# OLED.net
KiCad netlist of a schematic drawn in Altium Designer
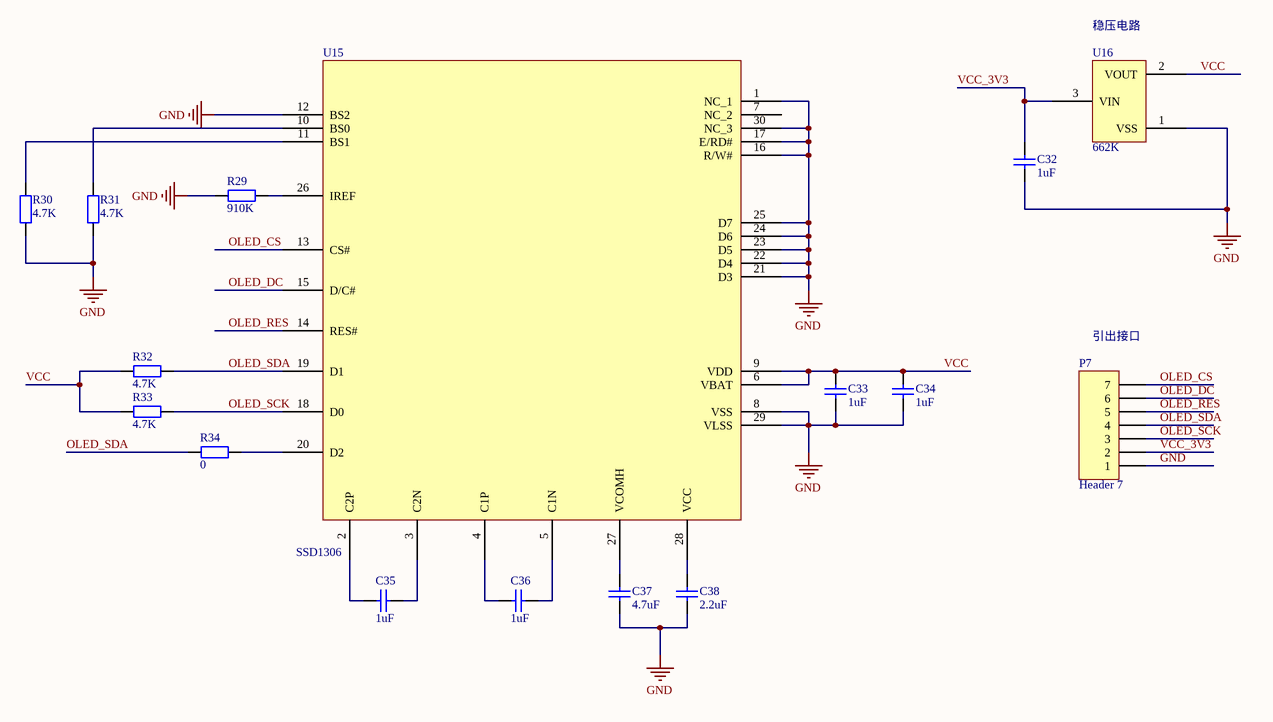
[diagram p0: OLED.SchDoc]

(export (version "E")
  (design (tool "Eeschema 10.0.6"))
  (components
    (comp (ref "C32")
      (value "1uF")
      (footprint "C0805_L")
      (description "贴片电容/MLCC电容")
      (libsource (lib "0.1 - 电阻-电容-电感-保险丝-晶振-晶体-磁珠-电位器-法拉电容-馈通电容") (part "C"))
    )
    (comp (ref "C33")
      (value "1uF")
      (footprint "C0805_L")
      (description "贴片电容/MLCC电容")
      (libsource (lib "0.1 - 电阻-电容-电感-保险丝-晶振-晶体-磁珠-电位器-法拉电容-馈通电容") (part "C"))
    )
    (comp (ref "C34")
      (value "1uF")
      (footprint "C0805_L")
      (description "贴片电容/MLCC电容")
      (libsource (lib "0.1 - 电阻-电容-电感-保险丝-晶振-晶体-磁珠-电位器-法拉电容-馈通电容") (part "C"))
    )
    (comp (ref "C35")
      (value "1uF")
      (footprint "C0805_L")
      (description "贴片电容/MLCC电容")
      (libsource (lib "0.1 - 电阻-电容-电感-保险丝-晶振-晶体-磁珠-电位器-法拉电容-馈通电容") (part "C"))
    )
    (comp (ref "C36")
      (value "1uF")
      (footprint "C0805_L")
      (description "贴片电容/MLCC电容")
      (libsource (lib "0.1 - 电阻-电容-电感-保险丝-晶振-晶体-磁珠-电位器-法拉电容-馈通电容") (part "C"))
    )
    (comp (ref "C37")
      (value "4.7uF")
      (footprint "C0805_L")
      (description "贴片电容/MLCC电容")
      (libsource (lib "0.1 - 电阻-电容-电感-保险丝-晶振-晶体-磁珠-电位器-法拉电容-馈通电容") (part "C"))
    )
    (comp (ref "C38")
      (value "2.2uF")
      (footprint "C0805_L")
      (description "贴片电容/MLCC电容")
      (libsource (lib "0.1 - 电阻-电容-电感-保险丝-晶振-晶体-磁珠-电位器-法拉电容-馈通电容") (part "C"))
    )
    (comp (ref "P7")
      (value "Header 7")
      (footprint "HDR1X7")
      (description "Header, 7-Pin")
      (fields (field (name "PUBLISHER") "Altium Limited"))
      (libsource (lib "Miscellaneous Connectors") (part "Header 7"))
    )
    (comp (ref "R29")
      (value "910K")
      (footprint "R0805_L")
      (description "贴片电阻")
      (libsource (lib "0.1 - 电阻-电容-电感-保险丝-晶振-晶体-磁珠-电位器-法拉电容-馈通电容") (part "R"))
    )
    (comp (ref "R30")
      (value "4.7K")
      (footprint "R0805_L")
      (description "贴片电阻")
      (libsource (lib "0.1 - 电阻-电容-电感-保险丝-晶振-晶体-磁珠-电位器-法拉电容-馈通电容") (part "R"))
    )
    (comp (ref "R31")
      (value "4.7K")
      (footprint "R0805_L")
      (description "贴片电阻")
      (libsource (lib "0.1 - 电阻-电容-电感-保险丝-晶振-晶体-磁珠-电位器-法拉电容-馈通电容") (part "R"))
    )
    (comp (ref "R32")
      (value "4.7K")
      (footprint "R0805_L")
      (description "贴片电阻")
      (libsource (lib "0.1 - 电阻-电容-电感-保险丝-晶振-晶体-磁珠-电位器-法拉电容-馈通电容") (part "R"))
    )
    (comp (ref "R33")
      (value "4.7K")
      (footprint "R0805_L")
      (description "贴片电阻")
      (libsource (lib "0.1 - 电阻-电容-电感-保险丝-晶振-晶体-磁珠-电位器-法拉电容-馈通电容") (part "R"))
    )
    (comp (ref "R34")
      (value "0")
      (footprint "R0805_L")
      (description "贴片电阻")
      (libsource (lib "0.1 - 电阻-电容-电感-保险丝-晶振-晶体-磁珠-电位器-法拉电容-馈通电容") (part "R"))
    )
    (comp (ref "U15") (value "SSD1306") (libsource (lib "OLED") (part "SSD1306")))
    (comp (ref "U16") (value "662K") (libsource (lib "OLED") (part "662K")))
  )
  (nets
    (net (code "1") (name "/OLED_CS") (class "Default")
      (node (ref "P7") (pin "7") (pinfunction "7_7") (pintype "passive"))
      (node (ref "U15") (pin "13") (pinfunction "CS#_13") (pintype "passive"))
    )
    (net (code "2") (name "/OLED_DC") (class "Default")
      (node (ref "P7") (pin "6") (pinfunction "6_6") (pintype "passive"))
      (node (ref "U15") (pin "15") (pinfunction "D/C#_15") (pintype "passive"))
    )
    (net (code "3") (name "/OLED_RES") (class "Default")
      (node (ref "P7") (pin "5") (pinfunction "5_5") (pintype "passive"))
      (node (ref "U15") (pin "14") (pinfunction "RES#_14") (pintype "passive"))
    )
    (net (code "4") (name "/OLED_SCK") (class "Default")
      (node (ref "P7") (pin "3") (pinfunction "3_3") (pintype "passive"))
      (node (ref "R33") (pin "1") (pinfunction "1_1") (pintype "passive"))
      (node (ref "U15") (pin "18") (pinfunction "D0_18") (pintype "passive"))
    )
    (net (code "5") (name "/OLED_SDA") (class "Default")
      (node (ref "P7") (pin "4") (pinfunction "4_4") (pintype "passive"))
      (node (ref "R32") (pin "1") (pinfunction "1_1") (pintype "passive"))
      (node (ref "R34") (pin "1") (pinfunction "1_1") (pintype "passive"))
      (node (ref "U15") (pin "19") (pinfunction "D1_19") (pintype "passive"))
    )
    (net (code "6") (name "/VCC") (class "Default")
      (node (ref "C33") (pin "1") (pinfunction "1_1") (pintype "passive"))
      (node (ref "C34") (pin "1") (pinfunction "1_1") (pintype "passive"))
      (node (ref "R32") (pin "2") (pinfunction "2_2") (pintype "passive"))
      (node (ref "R33") (pin "2") (pinfunction "2_2") (pintype "passive"))
      (node (ref "U15") (pin "6") (pinfunction "VBAT_6") (pintype "passive"))
      (node (ref "U15") (pin "9") (pinfunction "VDD_9") (pintype "passive"))
      (node (ref "U16") (pin "2") (pinfunction "VOUT_2") (pintype "passive"))
    )
    (net (code "7") (name "/VCC_3V3") (class "Default")
      (node (ref "C32") (pin "2") (pinfunction "2_2") (pintype "passive"))
      (node (ref "P7") (pin "2") (pinfunction "2_2") (pintype "passive"))
      (node (ref "U16") (pin "3") (pinfunction "VIN_3") (pintype "passive"))
    )
    (net (code "8") (name "GND") (class "Default")
      (node (ref "C32") (pin "1") (pinfunction "1_1") (pintype "passive"))
      (node (ref "C33") (pin "2") (pinfunction "2_2") (pintype "passive"))
      (node (ref "C34") (pin "2") (pinfunction "2_2") (pintype "passive"))
      (node (ref "C37") (pin "2") (pinfunction "2_2") (pintype "passive"))
      (node (ref "C38") (pin "2") (pinfunction "2_2") (pintype "passive"))
      (node (ref "P7") (pin "1") (pinfunction "1_1") (pintype "passive"))
      (node (ref "R29") (pin "2") (pinfunction "2_2") (pintype "passive"))
      (node (ref "R30") (pin "1") (pinfunction "1_1") (pintype "passive"))
      (node (ref "R31") (pin "1") (pinfunction "1_1") (pintype "passive"))
      (node (ref "U15") (pin "1") (pinfunction "NC_1_1") (pintype "passive"))
      (node (ref "U15") (pin "12") (pinfunction "BS2_12") (pintype "passive"))
      (node (ref "U15") (pin "16") (pinfunction "R/W#_16") (pintype "passive"))
      (node (ref "U15") (pin "17") (pinfunction "E/RD#_17") (pintype "passive"))
      (node (ref "U15") (pin "21") (pinfunction "D3_21") (pintype "passive"))
      (node (ref "U15") (pin "22") (pinfunction "D4_22") (pintype "passive"))
      (node (ref "U15") (pin "23") (pinfunction "D5_23") (pintype "passive"))
      (node (ref "U15") (pin "24") (pinfunction "D6_24") (pintype "passive"))
      (node (ref "U15") (pin "25") (pinfunction "D7_25") (pintype "passive"))
      (node (ref "U15") (pin "29") (pinfunction "VLSS_29") (pintype "passive"))
      (node (ref "U15") (pin "30") (pinfunction "NC_3_30") (pintype "passive"))
      (node (ref "U15") (pin "8") (pinfunction "VSS_8") (pintype "passive"))
      (node (ref "U16") (pin "1") (pinfunction "VSS_1") (pintype "passive"))
    )
    (net (code "9") (name "Net-(U15-BS0)") (class "Default")
      (node (ref "R31") (pin "2") (pinfunction "2_2") (pintype "passive"))
      (node (ref "U15") (pin "10") (pinfunction "BS0_10") (pintype "passive"))
    )
    (net (code "10") (name "Net-(U15-BS1)") (class "Default")
      (node (ref "R30") (pin "2") (pinfunction "2_2") (pintype "passive"))
      (node (ref "U15") (pin "11") (pinfunction "BS1_11") (pintype "passive"))
    )
    (net (code "11") (name "Net-(U15-C1N)") (class "Default")
      (node (ref "C36") (pin "1") (pinfunction "1_1") (pintype "passive"))
      (node (ref "U15") (pin "5") (pinfunction "C1N_5") (pintype "passive"))
    )
    (net (code "12") (name "Net-(U15-C1P)") (class "Default")
      (node (ref "C36") (pin "2") (pinfunction "2_2") (pintype "passive"))
      (node (ref "U15") (pin "4") (pinfunction "C1P_4") (pintype "passive"))
    )
    (net (code "13") (name "Net-(U15-C2N)") (class "Default")
      (node (ref "C35") (pin "1") (pinfunction "1_1") (pintype "passive"))
      (node (ref "U15") (pin "3") (pinfunction "C2N_3") (pintype "passive"))
    )
    (net (code "14") (name "Net-(U15-C2P)") (class "Default")
      (node (ref "C35") (pin "2") (pinfunction "2_2") (pintype "passive"))
      (node (ref "U15") (pin "2") (pinfunction "C2P_2") (pintype "passive"))
    )
    (net (code "15") (name "Net-(U15-D2)") (class "Default")
      (node (ref "R34") (pin "2") (pinfunction "2_2") (pintype "passive"))
      (node (ref "U15") (pin "20") (pinfunction "D2_20") (pintype "passive"))
    )
    (net (code "16") (name "Net-(U15-IREF)") (class "Default")
      (node (ref "R29") (pin "1") (pinfunction "1_1") (pintype "passive"))
      (node (ref "U15") (pin "26") (pinfunction "IREF_26") (pintype "passive"))
    )
    (net (code "17") (name "Net-(U15-VCC)") (class "Default")
      (node (ref "C38") (pin "1") (pinfunction "1_1") (pintype "passive"))
      (node (ref "U15") (pin "28") (pinfunction "VCC_28") (pintype "passive"))
    )
    (net (code "18") (name "Net-(U15-VCOMH)") (class "Default")
      (node (ref "C37") (pin "1") (pinfunction "1_1") (pintype "passive"))
      (node (ref "U15") (pin "27") (pinfunction "VCOMH_27") (pintype "passive"))
    )
    (net (code "19") (name "unconnected-(U15-NC_2-Pad7)") (class "Default")
      (node (ref "U15") (pin "7") (pinfunction "NC_2_7") (pintype "passive"))
    )
  )
)
